# BuildUpons-OffsetLED.net
KiCad netlist of a schematic drawn in EAGLE
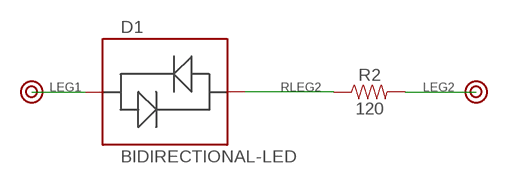
[diagram p0: schematic, sheet 1]

(export (version "E")
  (design (tool "Eeschema 10.0.6"))
  (components
    (comp (ref "D1")
      (value "BIDIRECTIONAL-LED")
      (footprint "eagle-import:BIDIRECTIONAL-LED")
      (libsource (lib "eagle-import") (part "BIDIRECTIONAL-LED"))
    )
    (comp (ref "J1")
      (value "METAL-LEGMOREPASTE")
      (footprint "eagle-import:METAL-LEG")
      (libsource (lib "eagle-import") (part "METAL-LEGMOREPASTE"))
    )
    (comp (ref "J2")
      (value "METAL-LEGMOREPASTE")
      (footprint "eagle-import:METAL-LEG")
      (libsource (lib "eagle-import") (part "METAL-LEGMOREPASTE"))
    )
    (comp (ref "R2")
      (value "120")
      (footprint "eagle-import:0402")
      (libsource (lib "eagle-import") (part "RESISTOR1"))
    )
  )
  (nets
    (net (code "1") (name "/LEG1") (class "Default")
      (node (ref "D1") (pin "LED1") (pinfunction "LED1_LED1") (pintype "bidirectional"))
      (node (ref "J1") (pin "1") (pinfunction "PIN1_1") (pintype "bidirectional"))
    )
    (net (code "2") (name "/LEG2") (class "Default")
      (node (ref "J2") (pin "1") (pinfunction "PIN1_1") (pintype "bidirectional"))
      (node (ref "R2") (pin "2") (pinfunction "2_2") (pintype "passive"))
    )
    (net (code "3") (name "/RLEG2") (class "Default")
      (node (ref "D1") (pin "LED2") (pinfunction "LED2_LED2") (pintype "bidirectional"))
      (node (ref "R2") (pin "1") (pinfunction "1_1") (pintype "passive"))
    )
  )
)
